# Schematic.net
KiCad netlist of a schematic drawn in Altium Designer
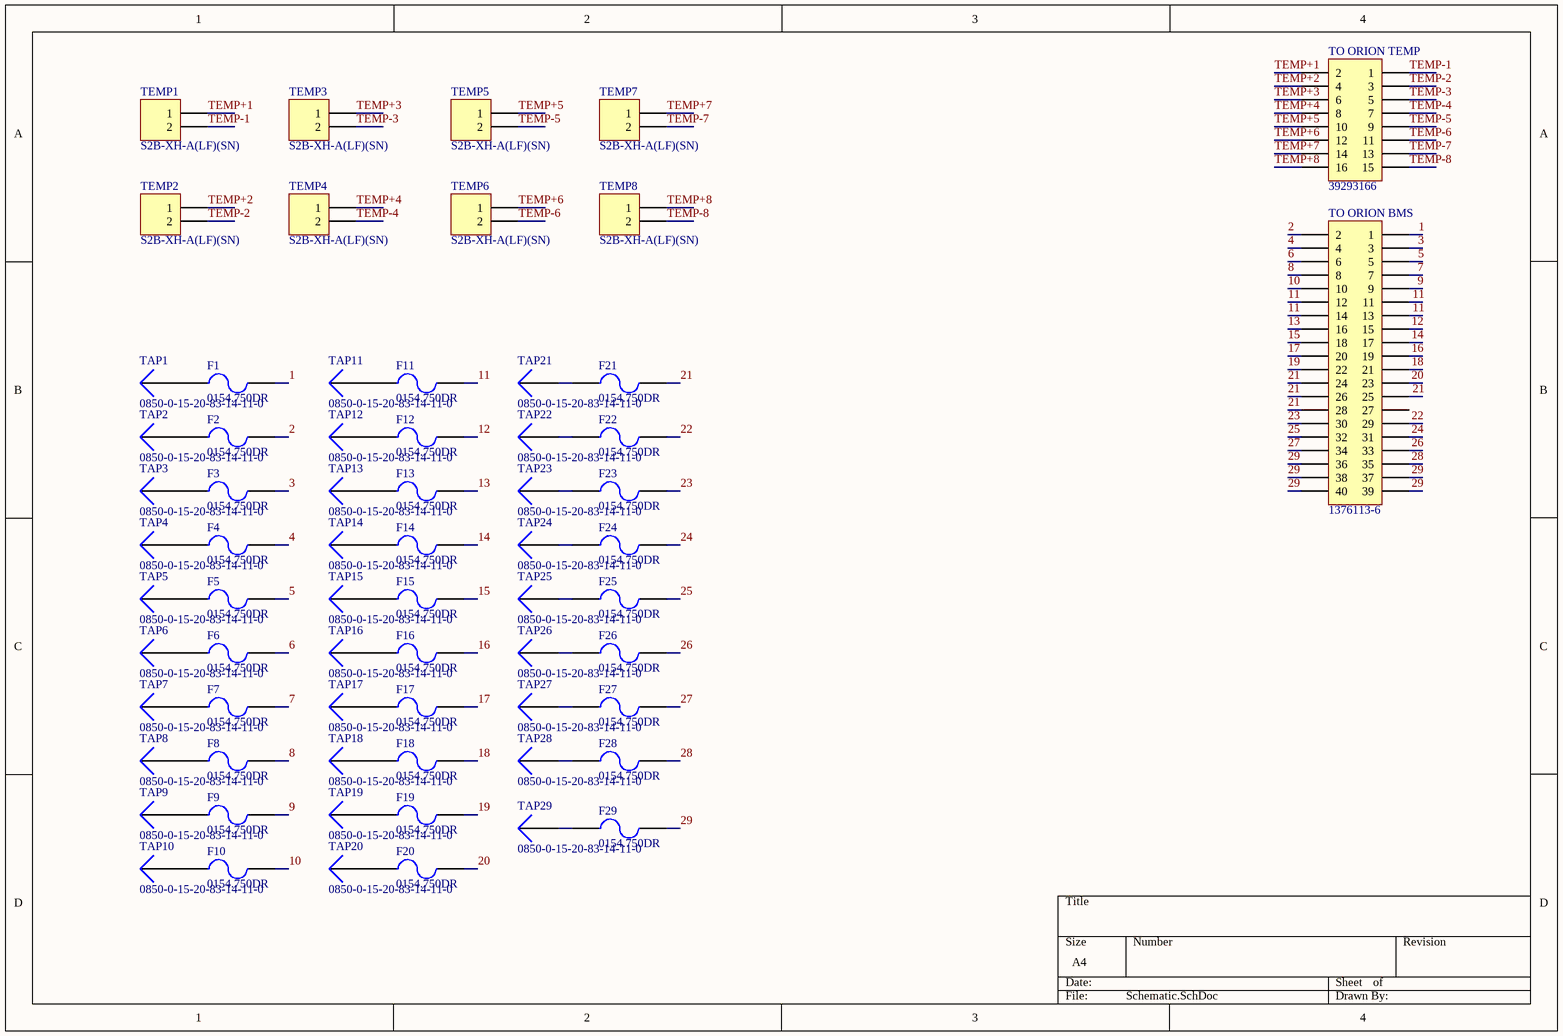
[diagram p0: Schematic.SchDoc]

(export (version "E")
  (design (tool "Eeschema 10.0.6"))
  (components
    (comp (ref "F1")
      (value "0154.750DR")
      (footprint "Omni BLOK 0154")
      (description "FUSE BOARD MNT 750MA 125VAC/VDC")
      (fields
        (field (name "MANUFACTURER") "LittelFuse Inc")
        (field (name "DIGIKEY PART NUMBER") "F1221CT-ND")
      )
      (libsource (lib "ts_20-standard-library") (part "Fuse"))
    )
    (comp (ref "F2")
      (value "0154.750DR")
      (footprint "Omni BLOK 0154")
      (description "FUSE BOARD MNT 750MA 125VAC/VDC")
      (fields
        (field (name "MANUFACTURER") "LittelFuse Inc")
        (field (name "DIGIKEY PART NUMBER") "F1221CT-ND")
      )
      (libsource (lib "ts_20-standard-library") (part "Fuse"))
    )
    (comp (ref "F3")
      (value "0154.750DR")
      (footprint "Omni BLOK 0154")
      (description "FUSE BOARD MNT 750MA 125VAC/VDC")
      (fields
        (field (name "MANUFACTURER") "LittelFuse Inc")
        (field (name "DIGIKEY PART NUMBER") "F1221CT-ND")
      )
      (libsource (lib "ts_20-standard-library") (part "Fuse"))
    )
    (comp (ref "F4")
      (value "0154.750DR")
      (footprint "Omni BLOK 0154")
      (description "FUSE BOARD MNT 750MA 125VAC/VDC")
      (fields
        (field (name "MANUFACTURER") "LittelFuse Inc")
        (field (name "DIGIKEY PART NUMBER") "F1221CT-ND")
      )
      (libsource (lib "ts_20-standard-library") (part "Fuse"))
    )
    (comp (ref "F5")
      (value "0154.750DR")
      (footprint "Omni BLOK 0154")
      (description "FUSE BOARD MNT 750MA 125VAC/VDC")
      (fields
        (field (name "MANUFACTURER") "LittelFuse Inc")
        (field (name "DIGIKEY PART NUMBER") "F1221CT-ND")
      )
      (libsource (lib "ts_20-standard-library") (part "Fuse"))
    )
    (comp (ref "F6")
      (value "0154.750DR")
      (footprint "Omni BLOK 0154")
      (description "FUSE BOARD MNT 750MA 125VAC/VDC")
      (fields
        (field (name "MANUFACTURER") "LittelFuse Inc")
        (field (name "DIGIKEY PART NUMBER") "F1221CT-ND")
      )
      (libsource (lib "ts_20-standard-library") (part "Fuse"))
    )
    (comp (ref "F7")
      (value "0154.750DR")
      (footprint "Omni BLOK 0154")
      (description "FUSE BOARD MNT 750MA 125VAC/VDC")
      (fields
        (field (name "MANUFACTURER") "LittelFuse Inc")
        (field (name "DIGIKEY PART NUMBER") "F1221CT-ND")
      )
      (libsource (lib "ts_20-standard-library") (part "Fuse"))
    )
    (comp (ref "F8")
      (value "0154.750DR")
      (footprint "Omni BLOK 0154")
      (description "FUSE BOARD MNT 750MA 125VAC/VDC")
      (fields
        (field (name "MANUFACTURER") "LittelFuse Inc")
        (field (name "DIGIKEY PART NUMBER") "F1221CT-ND")
      )
      (libsource (lib "ts_20-standard-library") (part "Fuse"))
    )
    (comp (ref "F9")
      (value "0154.750DR")
      (footprint "Omni BLOK 0154")
      (description "FUSE BOARD MNT 750MA 125VAC/VDC")
      (fields
        (field (name "MANUFACTURER") "LittelFuse Inc")
        (field (name "DIGIKEY PART NUMBER") "F1221CT-ND")
      )
      (libsource (lib "ts_20-standard-library") (part "Fuse"))
    )
    (comp (ref "F10")
      (value "0154.750DR")
      (footprint "Omni BLOK 0154")
      (description "FUSE BOARD MNT 750MA 125VAC/VDC")
      (fields
        (field (name "MANUFACTURER") "LittelFuse Inc")
        (field (name "DIGIKEY PART NUMBER") "F1221CT-ND")
      )
      (libsource (lib "ts_20-standard-library") (part "Fuse"))
    )
    (comp (ref "F11")
      (value "0154.750DR")
      (footprint "Omni BLOK 0154")
      (description "FUSE BOARD MNT 750MA 125VAC/VDC")
      (fields
        (field (name "MANUFACTURER") "LittelFuse Inc")
        (field (name "DIGIKEY PART NUMBER") "F1221CT-ND")
      )
      (libsource (lib "ts_20-standard-library") (part "Fuse"))
    )
    (comp (ref "F12")
      (value "0154.750DR")
      (footprint "Omni BLOK 0154")
      (description "FUSE BOARD MNT 750MA 125VAC/VDC")
      (fields
        (field (name "MANUFACTURER") "LittelFuse Inc")
        (field (name "DIGIKEY PART NUMBER") "F1221CT-ND")
      )
      (libsource (lib "ts_20-standard-library") (part "Fuse"))
    )
    (comp (ref "F13")
      (value "0154.750DR")
      (footprint "Omni BLOK 0154")
      (description "FUSE BOARD MNT 750MA 125VAC/VDC")
      (fields
        (field (name "MANUFACTURER") "LittelFuse Inc")
        (field (name "DIGIKEY PART NUMBER") "F1221CT-ND")
      )
      (libsource (lib "ts_20-standard-library") (part "Fuse"))
    )
    (comp (ref "F14")
      (value "0154.750DR")
      (footprint "Omni BLOK 0154")
      (description "FUSE BOARD MNT 750MA 125VAC/VDC")
      (fields
        (field (name "MANUFACTURER") "LittelFuse Inc")
        (field (name "DIGIKEY PART NUMBER") "F1221CT-ND")
      )
      (libsource (lib "ts_20-standard-library") (part "Fuse"))
    )
    (comp (ref "F15")
      (value "0154.750DR")
      (footprint "Omni BLOK 0154")
      (description "FUSE BOARD MNT 750MA 125VAC/VDC")
      (fields
        (field (name "MANUFACTURER") "LittelFuse Inc")
        (field (name "DIGIKEY PART NUMBER") "F1221CT-ND")
      )
      (libsource (lib "ts_20-standard-library") (part "Fuse"))
    )
    (comp (ref "F16")
      (value "0154.750DR")
      (footprint "Omni BLOK 0154")
      (description "FUSE BOARD MNT 750MA 125VAC/VDC")
      (fields
        (field (name "MANUFACTURER") "LittelFuse Inc")
        (field (name "DIGIKEY PART NUMBER") "F1221CT-ND")
      )
      (libsource (lib "ts_20-standard-library") (part "Fuse"))
    )
    (comp (ref "F17")
      (value "0154.750DR")
      (footprint "Omni BLOK 0154")
      (description "FUSE BOARD MNT 750MA 125VAC/VDC")
      (fields
        (field (name "MANUFACTURER") "LittelFuse Inc")
        (field (name "DIGIKEY PART NUMBER") "F1221CT-ND")
      )
      (libsource (lib "ts_20-standard-library") (part "Fuse"))
    )
    (comp (ref "F18")
      (value "0154.750DR")
      (footprint "Omni BLOK 0154")
      (description "FUSE BOARD MNT 750MA 125VAC/VDC")
      (fields
        (field (name "MANUFACTURER") "LittelFuse Inc")
        (field (name "DIGIKEY PART NUMBER") "F1221CT-ND")
      )
      (libsource (lib "ts_20-standard-library") (part "Fuse"))
    )
    (comp (ref "F19")
      (value "0154.750DR")
      (footprint "Omni BLOK 0154")
      (description "FUSE BOARD MNT 750MA 125VAC/VDC")
      (fields
        (field (name "MANUFACTURER") "LittelFuse Inc")
        (field (name "DIGIKEY PART NUMBER") "F1221CT-ND")
      )
      (libsource (lib "ts_20-standard-library") (part "Fuse"))
    )
    (comp (ref "F20")
      (value "0154.750DR")
      (footprint "Omni BLOK 0154")
      (description "FUSE BOARD MNT 750MA 125VAC/VDC")
      (fields
        (field (name "MANUFACTURER") "LittelFuse Inc")
        (field (name "DIGIKEY PART NUMBER") "F1221CT-ND")
      )
      (libsource (lib "ts_20-standard-library") (part "Fuse"))
    )
    (comp (ref "F21")
      (value "0154.750DR")
      (footprint "Omni BLOK 0154")
      (description "FUSE BOARD MNT 750MA 125VAC/VDC")
      (fields
        (field (name "MANUFACTURER") "LittelFuse Inc")
        (field (name "DIGIKEY PART NUMBER") "F1221CT-ND")
      )
      (libsource (lib "ts_20-standard-library") (part "Fuse"))
    )
    (comp (ref "F22")
      (value "0154.750DR")
      (footprint "Omni BLOK 0154")
      (description "FUSE BOARD MNT 750MA 125VAC/VDC")
      (fields
        (field (name "MANUFACTURER") "LittelFuse Inc")
        (field (name "DIGIKEY PART NUMBER") "F1221CT-ND")
      )
      (libsource (lib "ts_20-standard-library") (part "Fuse"))
    )
    (comp (ref "F23")
      (value "0154.750DR")
      (footprint "Omni BLOK 0154")
      (description "FUSE BOARD MNT 750MA 125VAC/VDC")
      (fields
        (field (name "MANUFACTURER") "LittelFuse Inc")
        (field (name "DIGIKEY PART NUMBER") "F1221CT-ND")
      )
      (libsource (lib "ts_20-standard-library") (part "Fuse"))
    )
    (comp (ref "F24")
      (value "0154.750DR")
      (footprint "Omni BLOK 0154")
      (description "FUSE BOARD MNT 750MA 125VAC/VDC")
      (fields
        (field (name "MANUFACTURER") "LittelFuse Inc")
        (field (name "DIGIKEY PART NUMBER") "F1221CT-ND")
      )
      (libsource (lib "ts_20-standard-library") (part "Fuse"))
    )
    (comp (ref "F25")
      (value "0154.750DR")
      (footprint "Omni BLOK 0154")
      (description "FUSE BOARD MNT 750MA 125VAC/VDC")
      (fields
        (field (name "MANUFACTURER") "LittelFuse Inc")
        (field (name "DIGIKEY PART NUMBER") "F1221CT-ND")
      )
      (libsource (lib "ts_20-standard-library") (part "Fuse"))
    )
    (comp (ref "F26")
      (value "0154.750DR")
      (footprint "Omni BLOK 0154")
      (description "FUSE BOARD MNT 750MA 125VAC/VDC")
      (fields
        (field (name "MANUFACTURER") "LittelFuse Inc")
        (field (name "DIGIKEY PART NUMBER") "F1221CT-ND")
      )
      (libsource (lib "ts_20-standard-library") (part "Fuse"))
    )
    (comp (ref "F27")
      (value "0154.750DR")
      (footprint "Omni BLOK 0154")
      (description "FUSE BOARD MNT 750MA 125VAC/VDC")
      (fields
        (field (name "MANUFACTURER") "LittelFuse Inc")
        (field (name "DIGIKEY PART NUMBER") "F1221CT-ND")
      )
      (libsource (lib "ts_20-standard-library") (part "Fuse"))
    )
    (comp (ref "F28")
      (value "0154.750DR")
      (footprint "Omni BLOK 0154")
      (description "FUSE BOARD MNT 750MA 125VAC/VDC")
      (fields
        (field (name "MANUFACTURER") "LittelFuse Inc")
        (field (name "DIGIKEY PART NUMBER") "F1221CT-ND")
      )
      (libsource (lib "ts_20-standard-library") (part "Fuse"))
    )
    (comp (ref "F29")
      (value "0154.750DR")
      (footprint "Omni BLOK 0154")
      (description "FUSE BOARD MNT 750MA 125VAC/VDC")
      (fields
        (field (name "MANUFACTURER") "LittelFuse Inc")
        (field (name "DIGIKEY PART NUMBER") "F1221CT-ND")
      )
      (libsource (lib "ts_20-standard-library") (part "Fuse"))
    )
    (comp (ref "TAP1")
      (value "0850-0-15-20-83-14-11-0")
      (footprint "0850-0-15-20-83-14-11-0")
      (fields (field (name "DIGIKEY PART NUMBER") "ED90436-ND") (field (name "CONTACT") "Gold"))
      (libsource (lib "ts_20-standard-connectors") (part "0850-0-15-20-83-14-11-0"))
    )
    (comp (ref "TAP2")
      (value "0850-0-15-20-83-14-11-0")
      (footprint "0850-0-15-20-83-14-11-0")
      (fields (field (name "DIGIKEY PART NUMBER") "ED90436-ND") (field (name "CONTACT") "Gold"))
      (libsource (lib "ts_20-standard-connectors") (part "0850-0-15-20-83-14-11-0"))
    )
    (comp (ref "TAP3")
      (value "0850-0-15-20-83-14-11-0")
      (footprint "0850-0-15-20-83-14-11-0")
      (fields (field (name "DIGIKEY PART NUMBER") "ED90436-ND") (field (name "CONTACT") "Gold"))
      (libsource (lib "ts_20-standard-connectors") (part "0850-0-15-20-83-14-11-0"))
    )
    (comp (ref "TAP4")
      (value "0850-0-15-20-83-14-11-0")
      (footprint "0850-0-15-20-83-14-11-0")
      (fields (field (name "DIGIKEY PART NUMBER") "ED90436-ND") (field (name "CONTACT") "Gold"))
      (libsource (lib "ts_20-standard-connectors") (part "0850-0-15-20-83-14-11-0"))
    )
    (comp (ref "TAP5")
      (value "0850-0-15-20-83-14-11-0")
      (footprint "0850-0-15-20-83-14-11-0")
      (fields (field (name "DIGIKEY PART NUMBER") "ED90436-ND") (field (name "CONTACT") "Gold"))
      (libsource (lib "ts_20-standard-connectors") (part "0850-0-15-20-83-14-11-0"))
    )
    (comp (ref "TAP6")
      (value "0850-0-15-20-83-14-11-0")
      (footprint "0850-0-15-20-83-14-11-0")
      (fields (field (name "DIGIKEY PART NUMBER") "ED90436-ND") (field (name "CONTACT") "Gold"))
      (libsource (lib "ts_20-standard-connectors") (part "0850-0-15-20-83-14-11-0"))
    )
    (comp (ref "TAP7")
      (value "0850-0-15-20-83-14-11-0")
      (footprint "0850-0-15-20-83-14-11-0")
      (fields (field (name "DIGIKEY PART NUMBER") "ED90436-ND") (field (name "CONTACT") "Gold"))
      (libsource (lib "ts_20-standard-connectors") (part "0850-0-15-20-83-14-11-0"))
    )
    (comp (ref "TAP8")
      (value "0850-0-15-20-83-14-11-0")
      (footprint "0850-0-15-20-83-14-11-0")
      (fields (field (name "DIGIKEY PART NUMBER") "ED90436-ND") (field (name "CONTACT") "Gold"))
      (libsource (lib "ts_20-standard-connectors") (part "0850-0-15-20-83-14-11-0"))
    )
    (comp (ref "TAP9")
      (value "0850-0-15-20-83-14-11-0")
      (footprint "0850-0-15-20-83-14-11-0")
      (fields (field (name "DIGIKEY PART NUMBER") "ED90436-ND") (field (name "CONTACT") "Gold"))
      (libsource (lib "ts_20-standard-connectors") (part "0850-0-15-20-83-14-11-0"))
    )
    (comp (ref "TAP10")
      (value "0850-0-15-20-83-14-11-0")
      (footprint "0850-0-15-20-83-14-11-0")
      (fields (field (name "DIGIKEY PART NUMBER") "ED90436-ND") (field (name "CONTACT") "Gold"))
      (libsource (lib "ts_20-standard-connectors") (part "0850-0-15-20-83-14-11-0"))
    )
    (comp (ref "TAP11")
      (value "0850-0-15-20-83-14-11-0")
      (footprint "0850-0-15-20-83-14-11-0")
      (fields (field (name "DIGIKEY PART NUMBER") "ED90436-ND") (field (name "CONTACT") "Gold"))
      (libsource (lib "ts_20-standard-connectors") (part "0850-0-15-20-83-14-11-0"))
    )
    (comp (ref "TAP12")
      (value "0850-0-15-20-83-14-11-0")
      (footprint "0850-0-15-20-83-14-11-0")
      (fields (field (name "DIGIKEY PART NUMBER") "ED90436-ND") (field (name "CONTACT") "Gold"))
      (libsource (lib "ts_20-standard-connectors") (part "0850-0-15-20-83-14-11-0"))
    )
    (comp (ref "TAP13")
      (value "0850-0-15-20-83-14-11-0")
      (footprint "0850-0-15-20-83-14-11-0")
      (fields (field (name "DIGIKEY PART NUMBER") "ED90436-ND") (field (name "CONTACT") "Gold"))
      (libsource (lib "ts_20-standard-connectors") (part "0850-0-15-20-83-14-11-0"))
    )
    (comp (ref "TAP14")
      (value "0850-0-15-20-83-14-11-0")
      (footprint "0850-0-15-20-83-14-11-0")
      (fields (field (name "DIGIKEY PART NUMBER") "ED90436-ND") (field (name "CONTACT") "Gold"))
      (libsource (lib "ts_20-standard-connectors") (part "0850-0-15-20-83-14-11-0"))
    )
    (comp (ref "TAP15")
      (value "0850-0-15-20-83-14-11-0")
      (footprint "0850-0-15-20-83-14-11-0")
      (fields (field (name "DIGIKEY PART NUMBER") "ED90436-ND") (field (name "CONTACT") "Gold"))
      (libsource (lib "ts_20-standard-connectors") (part "0850-0-15-20-83-14-11-0"))
    )
    (comp (ref "TAP16")
      (value "0850-0-15-20-83-14-11-0")
      (footprint "0850-0-15-20-83-14-11-0")
      (fields (field (name "DIGIKEY PART NUMBER") "ED90436-ND") (field (name "CONTACT") "Gold"))
      (libsource (lib "ts_20-standard-connectors") (part "0850-0-15-20-83-14-11-0"))
    )
    (comp (ref "TAP17")
      (value "0850-0-15-20-83-14-11-0")
      (footprint "0850-0-15-20-83-14-11-0")
      (fields (field (name "DIGIKEY PART NUMBER") "ED90436-ND") (field (name "CONTACT") "Gold"))
      (libsource (lib "ts_20-standard-connectors") (part "0850-0-15-20-83-14-11-0"))
    )
    (comp (ref "TAP18")
      (value "0850-0-15-20-83-14-11-0")
      (footprint "0850-0-15-20-83-14-11-0")
      (fields (field (name "DIGIKEY PART NUMBER") "ED90436-ND") (field (name "CONTACT") "Gold"))
      (libsource (lib "ts_20-standard-connectors") (part "0850-0-15-20-83-14-11-0"))
    )
    (comp (ref "TAP19")
      (value "0850-0-15-20-83-14-11-0")
      (footprint "0850-0-15-20-83-14-11-0")
      (fields (field (name "DIGIKEY PART NUMBER") "ED90436-ND") (field (name "CONTACT") "Gold"))
      (libsource (lib "ts_20-standard-connectors") (part "0850-0-15-20-83-14-11-0"))
    )
    (comp (ref "TAP20")
      (value "0850-0-15-20-83-14-11-0")
      (footprint "0850-0-15-20-83-14-11-0")
      (fields (field (name "DIGIKEY PART NUMBER") "ED90436-ND") (field (name "CONTACT") "Gold"))
      (libsource (lib "ts_20-standard-connectors") (part "0850-0-15-20-83-14-11-0"))
    )
    (comp (ref "TAP21")
      (value "0850-0-15-20-83-14-11-0")
      (footprint "0850-0-15-20-83-14-11-0")
      (fields (field (name "DIGIKEY PART NUMBER") "ED90436-ND") (field (name "CONTACT") "Gold"))
      (libsource (lib "ts_20-standard-connectors") (part "0850-0-15-20-83-14-11-0"))
    )
    (comp (ref "TAP22")
      (value "0850-0-15-20-83-14-11-0")
      (footprint "0850-0-15-20-83-14-11-0")
      (fields (field (name "DIGIKEY PART NUMBER") "ED90436-ND") (field (name "CONTACT") "Gold"))
      (libsource (lib "ts_20-standard-connectors") (part "0850-0-15-20-83-14-11-0"))
    )
    (comp (ref "TAP23")
      (value "0850-0-15-20-83-14-11-0")
      (footprint "0850-0-15-20-83-14-11-0")
      (fields (field (name "DIGIKEY PART NUMBER") "ED90436-ND") (field (name "CONTACT") "Gold"))
      (libsource (lib "ts_20-standard-connectors") (part "0850-0-15-20-83-14-11-0"))
    )
    (comp (ref "TAP24")
      (value "0850-0-15-20-83-14-11-0")
      (footprint "0850-0-15-20-83-14-11-0")
      (fields (field (name "DIGIKEY PART NUMBER") "ED90436-ND") (field (name "CONTACT") "Gold"))
      (libsource (lib "ts_20-standard-connectors") (part "0850-0-15-20-83-14-11-0"))
    )
    (comp (ref "TAP25")
      (value "0850-0-15-20-83-14-11-0")
      (footprint "0850-0-15-20-83-14-11-0")
      (fields (field (name "DIGIKEY PART NUMBER") "ED90436-ND") (field (name "CONTACT") "Gold"))
      (libsource (lib "ts_20-standard-connectors") (part "0850-0-15-20-83-14-11-0"))
    )
    (comp (ref "TAP26")
      (value "0850-0-15-20-83-14-11-0")
      (footprint "0850-0-15-20-83-14-11-0")
      (fields (field (name "DIGIKEY PART NUMBER") "ED90436-ND") (field (name "CONTACT") "Gold"))
      (libsource (lib "ts_20-standard-connectors") (part "0850-0-15-20-83-14-11-0"))
    )
    (comp (ref "TAP27")
      (value "0850-0-15-20-83-14-11-0")
      (footprint "0850-0-15-20-83-14-11-0")
      (fields (field (name "DIGIKEY PART NUMBER") "ED90436-ND") (field (name "CONTACT") "Gold"))
      (libsource (lib "ts_20-standard-connectors") (part "0850-0-15-20-83-14-11-0"))
    )
    (comp (ref "TAP28")
      (value "0850-0-15-20-83-14-11-0")
      (footprint "0850-0-15-20-83-14-11-0")
      (fields (field (name "DIGIKEY PART NUMBER") "ED90436-ND") (field (name "CONTACT") "Gold"))
      (libsource (lib "ts_20-standard-connectors") (part "0850-0-15-20-83-14-11-0"))
    )
    (comp (ref "TAP29")
      (value "0850-0-15-20-83-14-11-0")
      (footprint "0850-0-15-20-83-14-11-0")
      (fields (field (name "DIGIKEY PART NUMBER") "ED90436-ND") (field (name "CONTACT") "Gold"))
      (libsource (lib "ts_20-standard-connectors") (part "0850-0-15-20-83-14-11-0"))
    )
    (comp (ref "TEMP1") (value "S2B-XH-A(LF)(SN)") (libsource (lib "JST") (part "S2B-XH-A(LF)(SN)")))
    (comp (ref "TEMP2") (value "S2B-XH-A(LF)(SN)") (libsource (lib "JST") (part "S2B-XH-A(LF)(SN)")))
    (comp (ref "TEMP3") (value "S2B-XH-A(LF)(SN)") (libsource (lib "JST") (part "S2B-XH-A(LF)(SN)")))
    (comp (ref "TEMP4") (value "S2B-XH-A(LF)(SN)") (libsource (lib "JST") (part "S2B-XH-A(LF)(SN)")))
    (comp (ref "TEMP5") (value "S2B-XH-A(LF)(SN)") (libsource (lib "JST") (part "S2B-XH-A(LF)(SN)")))
    (comp (ref "TEMP6") (value "S2B-XH-A(LF)(SN)") (libsource (lib "JST") (part "S2B-XH-A(LF)(SN)")))
    (comp (ref "TEMP7") (value "S2B-XH-A(LF)(SN)") (libsource (lib "JST") (part "S2B-XH-A(LF)(SN)")))
    (comp (ref "TEMP8") (value "S2B-XH-A(LF)(SN)") (libsource (lib "JST") (part "S2B-XH-A(LF)(SN)")))
    (comp (ref "TO ORION BMS")
      (value "1376113-6")
      (footprint "1376113-6")
      (fields (field (name "DIGIKEY PART NUMBER") "A122206-ND") (field (name "CONTACT") "gold"))
      (libsource (lib "ts_20-standard-connectors") (part "1376113-6"))
    )
    (comp (ref "TO ORION TEMP")
      (value "39293166")
      (footprint "39293166")
      (description "8*2")
      (fields (field (name "DIGIKEY PART NUMBER") "WM3850-ND") (field (name "CONTACT") "Tin"))
      (libsource (lib "ts_20-standard-connectors") (part "39293166"))
    )
  )
  (nets
    (net (code "1") (name "/1") (class "Default")
      (node (ref "F1") (pin "2") (pinfunction "2_2") (pintype "passive"))
      (node (ref "TO ORION BMS") (pin "1") (pinfunction "1_1") (pintype "passive"))
    )
    (net (code "2") (name "/2") (class "Default")
      (node (ref "F2") (pin "2") (pinfunction "2_2") (pintype "passive"))
      (node (ref "TO ORION BMS") (pin "2") (pinfunction "2_2") (pintype "passive"))
    )
    (net (code "3") (name "/3") (class "Default")
      (node (ref "F3") (pin "2") (pinfunction "2_2") (pintype "passive"))
      (node (ref "TO ORION BMS") (pin "3") (pinfunction "3_3") (pintype "passive"))
    )
    (net (code "4") (name "/4") (class "Default")
      (node (ref "F4") (pin "2") (pinfunction "2_2") (pintype "passive"))
      (node (ref "TO ORION BMS") (pin "4") (pinfunction "4_4") (pintype "passive"))
    )
    (net (code "5") (name "/5") (class "Default")
      (node (ref "F5") (pin "2") (pinfunction "2_2") (pintype "passive"))
      (node (ref "TO ORION BMS") (pin "5") (pinfunction "5_5") (pintype "passive"))
    )
    (net (code "6") (name "/6") (class "Default")
      (node (ref "F6") (pin "2") (pinfunction "2_2") (pintype "passive"))
      (node (ref "TO ORION BMS") (pin "6") (pinfunction "6_6") (pintype "passive"))
    )
    (net (code "7") (name "/7") (class "Default")
      (node (ref "F7") (pin "2") (pinfunction "2_2") (pintype "passive"))
      (node (ref "TO ORION BMS") (pin "7") (pinfunction "7_7") (pintype "passive"))
    )
    (net (code "8") (name "/8") (class "Default")
      (node (ref "F8") (pin "2") (pinfunction "2_2") (pintype "passive"))
      (node (ref "TO ORION BMS") (pin "8") (pinfunction "8_8") (pintype "passive"))
    )
    (net (code "9") (name "/9") (class "Default")
      (node (ref "F9") (pin "2") (pinfunction "2_2") (pintype "passive"))
      (node (ref "TO ORION BMS") (pin "9") (pinfunction "9_9") (pintype "passive"))
    )
    (net (code "10") (name "/10") (class "Default")
      (node (ref "F10") (pin "2") (pinfunction "2_2") (pintype "passive"))
      (node (ref "TO ORION BMS") (pin "10") (pinfunction "10_10") (pintype "passive"))
    )
    (net (code "11") (name "/11") (class "Default")
      (node (ref "F11") (pin "2") (pinfunction "2_2") (pintype "passive"))
      (node (ref "TO ORION BMS") (pin "11") (pinfunction "11_11") (pintype "passive"))
      (node (ref "TO ORION BMS") (pin "12") (pinfunction "12_12") (pintype "passive"))
      (node (ref "TO ORION BMS") (pin "13") (pinfunction "13_13") (pintype "passive"))
      (node (ref "TO ORION BMS") (pin "14") (pinfunction "14_14") (pintype "passive"))
    )
    (net (code "12") (name "/12") (class "Default")
      (node (ref "F12") (pin "2") (pinfunction "2_2") (pintype "passive"))
      (node (ref "TO ORION BMS") (pin "15") (pinfunction "15_15") (pintype "passive"))
    )
    (net (code "13") (name "/13") (class "Default")
      (node (ref "F13") (pin "2") (pinfunction "2_2") (pintype "passive"))
      (node (ref "TO ORION BMS") (pin "16") (pinfunction "16_16") (pintype "passive"))
    )
    (net (code "14") (name "/14") (class "Default")
      (node (ref "F14") (pin "2") (pinfunction "2_2") (pintype "passive"))
      (node (ref "TO ORION BMS") (pin "17") (pinfunction "17_17") (pintype "passive"))
    )
    (net (code "15") (name "/15") (class "Default")
      (node (ref "F15") (pin "2") (pinfunction "2_2") (pintype "passive"))
      (node (ref "TO ORION BMS") (pin "18") (pinfunction "18_18") (pintype "passive"))
    )
    (net (code "16") (name "/16") (class "Default")
      (node (ref "F16") (pin "2") (pinfunction "2_2") (pintype "passive"))
      (node (ref "TO ORION BMS") (pin "19") (pinfunction "19_19") (pintype "passive"))
    )
    (net (code "17") (name "/17") (class "Default")
      (node (ref "F17") (pin "2") (pinfunction "2_2") (pintype "passive"))
      (node (ref "TO ORION BMS") (pin "20") (pinfunction "20_20") (pintype "passive"))
    )
    (net (code "18") (name "/18") (class "Default")
      (node (ref "F18") (pin "2") (pinfunction "2_2") (pintype "passive"))
      (node (ref "TO ORION BMS") (pin "21") (pinfunction "21_21") (pintype "passive"))
    )
    (net (code "19") (name "/19") (class "Default")
      (node (ref "F19") (pin "2") (pinfunction "2_2") (pintype "passive"))
      (node (ref "TO ORION BMS") (pin "22") (pinfunction "22_22") (pintype "passive"))
    )
    (net (code "20") (name "/20") (class "Default")
      (node (ref "F20") (pin "2") (pinfunction "2_2") (pintype "passive"))
      (node (ref "TO ORION BMS") (pin "23") (pinfunction "23_23") (pintype "passive"))
    )
    (net (code "21") (name "/21") (class "Default")
      (node (ref "F21") (pin "2") (pinfunction "2_2") (pintype "passive"))
      (node (ref "TO ORION BMS") (pin "24") (pinfunction "24_24") (pintype "passive"))
      (node (ref "TO ORION BMS") (pin "25") (pinfunction "25_25") (pintype "passive"))
      (node (ref "TO ORION BMS") (pin "26") (pinfunction "26_26") (pintype "passive"))
      (node (ref "TO ORION BMS") (pin "28") (pinfunction "28_28") (pintype "passive"))
    )
    (net (code "22") (name "/22") (class "Default")
      (node (ref "F22") (pin "2") (pinfunction "2_2") (pintype "passive"))
      (node (ref "TO ORION BMS") (pin "29") (pinfunction "29_29") (pintype "passive"))
    )
    (net (code "23") (name "/23") (class "Default")
      (node (ref "F23") (pin "2") (pinfunction "2_2") (pintype "passive"))
      (node (ref "TO ORION BMS") (pin "30") (pinfunction "30_30") (pintype "passive"))
    )
    (net (code "24") (name "/24") (class "Default")
      (node (ref "F24") (pin "2") (pinfunction "2_2") (pintype "passive"))
      (node (ref "TO ORION BMS") (pin "31") (pinfunction "31_31") (pintype "passive"))
    )
    (net (code "25") (name "/25") (class "Default")
      (node (ref "F25") (pin "2") (pinfunction "2_2") (pintype "passive"))
      (node (ref "TO ORION BMS") (pin "32") (pinfunction "32_32") (pintype "passive"))
    )
    (net (code "26") (name "/26") (class "Default")
      (node (ref "F26") (pin "2") (pinfunction "2_2") (pintype "passive"))
      (node (ref "TO ORION BMS") (pin "33") (pinfunction "33_33") (pintype "passive"))
    )
    (net (code "27") (name "/27") (class "Default")
      (node (ref "F27") (pin "2") (pinfunction "2_2") (pintype "passive"))
      (node (ref "TO ORION BMS") (pin "34") (pinfunction "34_34") (pintype "passive"))
    )
    (net (code "28") (name "/28") (class "Default")
      (node (ref "F28") (pin "2") (pinfunction "2_2") (pintype "passive"))
      (node (ref "TO ORION BMS") (pin "35") (pinfunction "35_35") (pintype "passive"))
    )
    (net (code "29") (name "/29") (class "Default")
      (node (ref "F29") (pin "2") (pinfunction "2_2") (pintype "passive"))
      (node (ref "TO ORION BMS") (pin "36") (pinfunction "36_36") (pintype "passive"))
      (node (ref "TO ORION BMS") (pin "37") (pinfunction "37_37") (pintype "passive"))
      (node (ref "TO ORION BMS") (pin "38") (pinfunction "38_38") (pintype "passive"))
      (node (ref "TO ORION BMS") (pin "39") (pinfunction "39_39") (pintype "passive"))
      (node (ref "TO ORION BMS") (pin "40") (pinfunction "40_40") (pintype "passive"))
    )
    (net (code "30") (name "/TEMP+1") (class "Default")
      (node (ref "TEMP1") (pin "1") (pinfunction "1_1") (pintype "passive"))
      (node (ref "TO ORION TEMP") (pin "2") (pinfunction "2_2") (pintype "passive"))
    )
    (net (code "31") (name "/TEMP+2") (class "Default")
      (node (ref "TEMP2") (pin "1") (pinfunction "1_1") (pintype "passive"))
      (node (ref "TO ORION TEMP") (pin "4") (pinfunction "4_4") (pintype "passive"))
    )
    (net (code "32") (name "/TEMP+3") (class "Default")
      (node (ref "TEMP3") (pin "1") (pinfunction "1_1") (pintype "passive"))
      (node (ref "TO ORION TEMP") (pin "6") (pinfunction "6_6") (pintype "passive"))
    )
    (net (code "33") (name "/TEMP+4") (class "Default")
      (node (ref "TEMP4") (pin "1") (pinfunction "1_1") (pintype "passive"))
      (node (ref "TO ORION TEMP") (pin "8") (pinfunction "8_8") (pintype "passive"))
    )
    (net (code "34") (name "/TEMP+5") (class "Default")
      (node (ref "TEMP5") (pin "1") (pinfunction "1_1") (pintype "passive"))
      (node (ref "TO ORION TEMP") (pin "10") (pinfunction "10_10") (pintype "passive"))
    )
    (net (code "35") (name "/TEMP+6") (class "Default")
      (node (ref "TEMP6") (pin "1") (pinfunction "1_1") (pintype "passive"))
      (node (ref "TO ORION TEMP") (pin "12") (pinfunction "12_12") (pintype "passive"))
    )
    (net (code "36") (name "/TEMP+7") (class "Default")
      (node (ref "TEMP7") (pin "1") (pinfunction "1_1") (pintype "passive"))
      (node (ref "TO ORION TEMP") (pin "14") (pinfunction "14_14") (pintype "passive"))
    )
    (net (code "37") (name "/TEMP+8") (class "Default")
      (node (ref "TEMP8") (pin "1") (pinfunction "1_1") (pintype "passive"))
      (node (ref "TO ORION TEMP") (pin "16") (pinfunction "16_16") (pintype "passive"))
    )
    (net (code "38") (name "/TEMP-1") (class "Default")
      (node (ref "TEMP1") (pin "2") (pinfunction "2_2") (pintype "passive"))
      (node (ref "TO ORION TEMP") (pin "1") (pinfunction "1_1") (pintype "passive"))
    )
    (net (code "39") (name "/TEMP-2") (class "Default")
      (node (ref "TEMP2") (pin "2") (pinfunction "2_2") (pintype "passive"))
      (node (ref "TO ORION TEMP") (pin "3") (pinfunction "3_3") (pintype "passive"))
    )
    (net (code "40") (name "/TEMP-3") (class "Default")
      (node (ref "TEMP3") (pin "2") (pinfunction "2_2") (pintype "passive"))
      (node (ref "TO ORION TEMP") (pin "5") (pinfunction "5_5") (pintype "passive"))
    )
    (net (code "41") (name "/TEMP-4") (class "Default")
      (node (ref "TEMP4") (pin "2") (pinfunction "2_2") (pintype "passive"))
      (node (ref "TO ORION TEMP") (pin "7") (pinfunction "7_7") (pintype "passive"))
    )
    (net (code "42") (name "/TEMP-5") (class "Default")
      (node (ref "TEMP5") (pin "2") (pinfunction "2_2") (pintype "passive"))
      (node (ref "TO ORION TEMP") (pin "9") (pinfunction "9_9") (pintype "passive"))
    )
    (net (code "43") (name "/TEMP-6") (class "Default")
      (node (ref "TEMP6") (pin "2") (pinfunction "2_2") (pintype "passive"))
      (node (ref "TO ORION TEMP") (pin "11") (pinfunction "11_11") (pintype "passive"))
    )
    (net (code "44") (name "/TEMP-7") (class "Default")
      (node (ref "TEMP7") (pin "2") (pinfunction "2_2") (pintype "passive"))
      (node (ref "TO ORION TEMP") (pin "13") (pinfunction "13_13") (pintype "passive"))
    )
    (net (code "45") (name "/TEMP-8") (class "Default")
      (node (ref "TEMP8") (pin "2") (pinfunction "2_2") (pintype "passive"))
      (node (ref "TO ORION TEMP") (pin "15") (pinfunction "15_15") (pintype "passive"))
    )
    (net (code "46") (name "Net-(TAP1-=\"part_number\")") (class "Default")
      (node (ref "F1") (pin "1") (pinfunction "1_1") (pintype "passive"))
      (node (ref "TAP1") (pin "1") (pinfunction "=\"part_number\"_1") (pintype "passive"))
    )
    (net (code "47") (name "Net-(TAP2-=\"part_number\")") (class "Default")
      (node (ref "F2") (pin "1") (pinfunction "1_1") (pintype "passive"))
      (node (ref "TAP2") (pin "1") (pinfunction "=\"part_number\"_1") (pintype "passive"))
    )
    (net (code "48") (name "Net-(TAP3-=\"part_number\")") (class "Default")
      (node (ref "F3") (pin "1") (pinfunction "1_1") (pintype "passive"))
      (node (ref "TAP3") (pin "1") (pinfunction "=\"part_number\"_1") (pintype "passive"))
    )
    (net (code "49") (name "Net-(TAP4-=\"part_number\")") (class "Default")
      (node (ref "F4") (pin "1") (pinfunction "1_1") (pintype "passive"))
      (node (ref "TAP4") (pin "1") (pinfunction "=\"part_number\"_1") (pintype "passive"))
    )
    (net (code "50") (name "Net-(TAP5-=\"part_number\")") (class "Default")
      (node (ref "F5") (pin "1") (pinfunction "1_1") (pintype "passive"))
      (node (ref "TAP5") (pin "1") (pinfunction "=\"part_number\"_1") (pintype "passive"))
    )
    (net (code "51") (name "Net-(TAP6-=\"part_number\")") (class "Default")
      (node (ref "F6") (pin "1") (pinfunction "1_1") (pintype "passive"))
      (node (ref "TAP6") (pin "1") (pinfunction "=\"part_number\"_1") (pintype "passive"))
    )
    (net (code "52") (name "Net-(TAP7-=\"part_number\")") (class "Default")
      (node (ref "F7") (pin "1") (pinfunction "1_1") (pintype "passive"))
      (node (ref "TAP7") (pin "1") (pinfunction "=\"part_number\"_1") (pintype "passive"))
    )
    (net (code "53") (name "Net-(TAP8-=\"part_number\")") (class "Default")
      (node (ref "F8") (pin "1") (pinfunction "1_1") (pintype "passive"))
      (node (ref "TAP8") (pin "1") (pinfunction "=\"part_number\"_1") (pintype "passive"))
    )
    (net (code "54") (name "Net-(TAP9-=\"part_number\")") (class "Default")
      (node (ref "F9") (pin "1") (pinfunction "1_1") (pintype "passive"))
      (node (ref "TAP9") (pin "1") (pinfunction "=\"part_number\"_1") (pintype "passive"))
    )
    (net (code "55") (name "Net-(TAP10-=\"part_number\")") (class "Default")
      (node (ref "F10") (pin "1") (pinfunction "1_1") (pintype "passive"))
      (node (ref "TAP10") (pin "1") (pinfunction "=\"part_number\"_1") (pintype "passive"))
    )
    (net (code "56") (name "Net-(TAP11-=\"part_number\")") (class "Default")
      (node (ref "F11") (pin "1") (pinfunction "1_1") (pintype "passive"))
      (node (ref "TAP11") (pin "1") (pinfunction "=\"part_number\"_1") (pintype "passive"))
    )
    (net (code "57") (name "Net-(TAP12-=\"part_number\")") (class "Default")
      (node (ref "F12") (pin "1") (pinfunction "1_1") (pintype "passive"))
      (node (ref "TAP12") (pin "1") (pinfunction "=\"part_number\"_1") (pintype "passive"))
    )
    (net (code "58") (name "Net-(TAP13-=\"part_number\")") (class "Default")
      (node (ref "F13") (pin "1") (pinfunction "1_1") (pintype "passive"))
      (node (ref "TAP13") (pin "1") (pinfunction "=\"part_number\"_1") (pintype "passive"))
    )
    (net (code "59") (name "Net-(TAP14-=\"part_number\")") (class "Default")
      (node (ref "F14") (pin "1") (pinfunction "1_1") (pintype "passive"))
      (node (ref "TAP14") (pin "1") (pinfunction "=\"part_number\"_1") (pintype "passive"))
    )
    (net (code "60") (name "Net-(TAP15-=\"part_number\")") (class "Default")
      (node (ref "F15") (pin "1") (pinfunction "1_1") (pintype "passive"))
      (node (ref "TAP15") (pin "1") (pinfunction "=\"part_number\"_1") (pintype "passive"))
    )
    (net (code "61") (name "Net-(TAP16-=\"part_number\")") (class "Default")
      (node (ref "F16") (pin "1") (pinfunction "1_1") (pintype "passive"))
      (node (ref "TAP16") (pin "1") (pinfunction "=\"part_number\"_1") (pintype "passive"))
    )
    (net (code "62") (name "Net-(TAP17-=\"part_number\")") (class "Default")
      (node (ref "F17") (pin "1") (pinfunction "1_1") (pintype "passive"))
      (node (ref "TAP17") (pin "1") (pinfunction "=\"part_number\"_1") (pintype "passive"))
    )
    (net (code "63") (name "Net-(TAP18-=\"part_number\")") (class "Default")
      (node (ref "F18") (pin "1") (pinfunction "1_1") (pintype "passive"))
      (node (ref "TAP18") (pin "1") (pinfunction "=\"part_number\"_1") (pintype "passive"))
    )
    (net (code "64") (name "Net-(TAP19-=\"part_number\")") (class "Default")
      (node (ref "F19") (pin "1") (pinfunction "1_1") (pintype "passive"))
      (node (ref "TAP19") (pin "1") (pinfunction "=\"part_number\"_1") (pintype "passive"))
    )
    (net (code "65") (name "Net-(TAP20-=\"part_number\")") (class "Default")
      (node (ref "F20") (pin "1") (pinfunction "1_1") (pintype "passive"))
      (node (ref "TAP20") (pin "1") (pinfunction "=\"part_number\"_1") (pintype "passive"))
    )
    (net (code "66") (name "Net-(TAP21-=\"part_number\")") (class "Default")
      (node (ref "F21") (pin "1") (pinfunction "1_1") (pintype "passive"))
      (node (ref "TAP21") (pin "1") (pinfunction "=\"part_number\"_1") (pintype "passive"))
    )
    (net (code "67") (name "Net-(TAP22-=\"part_number\")") (class "Default")
      (node (ref "F22") (pin "1") (pinfunction "1_1") (pintype "passive"))
      (node (ref "TAP22") (pin "1") (pinfunction "=\"part_number\"_1") (pintype "passive"))
    )
    (net (code "68") (name "Net-(TAP23-=\"part_number\")") (class "Default")
      (node (ref "F23") (pin "1") (pinfunction "1_1") (pintype "passive"))
      (node (ref "TAP23") (pin "1") (pinfunction "=\"part_number\"_1") (pintype "passive"))
    )
    (net (code "69") (name "Net-(TAP24-=\"part_number\")") (class "Default")
      (node (ref "F24") (pin "1") (pinfunction "1_1") (pintype "passive"))
      (node (ref "TAP24") (pin "1") (pinfunction "=\"part_number\"_1") (pintype "passive"))
    )
    (net (code "70") (name "Net-(TAP25-=\"part_number\")") (class "Default")
      (node (ref "F25") (pin "1") (pinfunction "1_1") (pintype "passive"))
      (node (ref "TAP25") (pin "1") (pinfunction "=\"part_number\"_1") (pintype "passive"))
    )
    (net (code "71") (name "Net-(TAP26-=\"part_number\")") (class "Default")
      (node (ref "F26") (pin "1") (pinfunction "1_1") (pintype "passive"))
      (node (ref "TAP26") (pin "1") (pinfunction "=\"part_number\"_1") (pintype "passive"))
    )
    (net (code "72") (name "Net-(TAP27-=\"part_number\")") (class "Default")
      (node (ref "F27") (pin "1") (pinfunction "1_1") (pintype "passive"))
      (node (ref "TAP27") (pin "1") (pinfunction "=\"part_number\"_1") (pintype "passive"))
    )
    (net (code "73") (name "Net-(TAP28-=\"part_number\")") (class "Default")
      (node (ref "F28") (pin "1") (pinfunction "1_1") (pintype "passive"))
      (node (ref "TAP28") (pin "1") (pinfunction "=\"part_number\"_1") (pintype "passive"))
    )
    (net (code "74") (name "Net-(TAP29-=\"part_number\")") (class "Default")
      (node (ref "F29") (pin "1") (pinfunction "1_1") (pintype "passive"))
      (node (ref "TAP29") (pin "1") (pinfunction "=\"part_number\"_1") (pintype "passive"))
    )
    (net (code "75") (name "unconnected-(TO ORION BMS-Pad27)") (class "Default")
      (node (ref "TO ORION BMS") (pin "27") (pinfunction "27_27") (pintype "passive"))
    )
  )
)
